# LED_MAINBOARD.net
KiCad netlist of a schematic drawn in Altium Designer
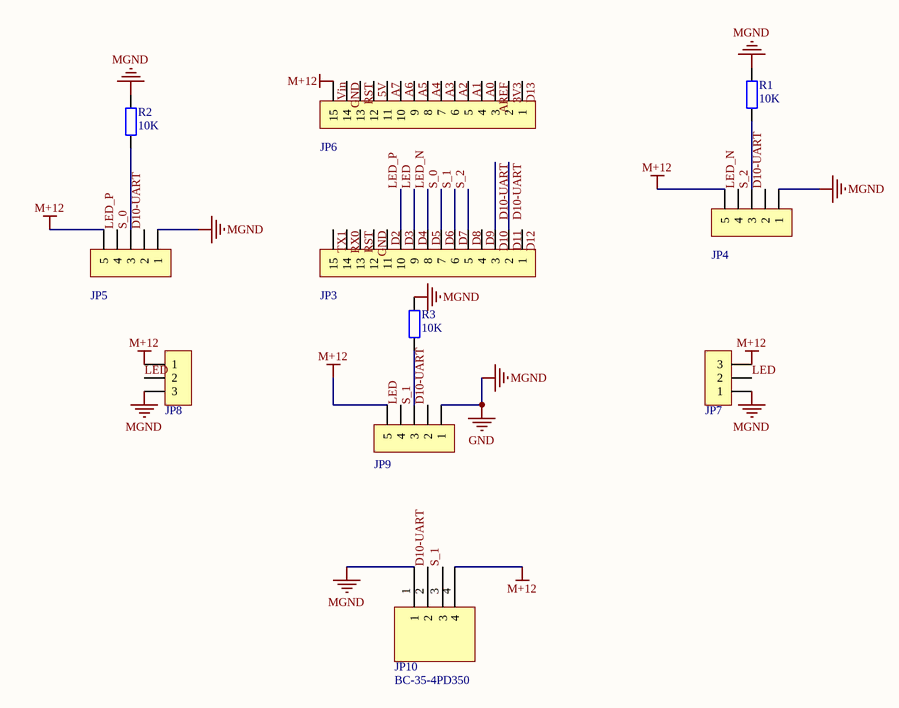
[diagram p0: LED_MAINBOARD.SchDoc]

(export (version "E")
  (design (tool "Eeschema 10.0.6"))
  (components
    (comp (ref "JP3")
      (value "HDR-1X15")
      (footprint "HDR2.54-M-LI-15P")
      (description "15P接插件")
      (fields (field (name "版权归属") "源创客"))
      (libsource (lib "4.6   - 接插件-脚距2.54") (part "Header 15"))
    )
    (comp (ref "JP4")
      (value "HDR-1X5")
      (footprint "ZH1.5-WS-5P")
      (description "5P接插件")
      (fields (field (name "版权归属") "源创客"))
      (libsource (lib "4.4   - 接插件-脚距1.5") (part "Header 5"))
    )
    (comp (ref "JP5")
      (value "HDR-1X5")
      (footprint "ZH1.5-WS-5P")
      (description "5P接插件")
      (fields (field (name "版权归属") "源创客"))
      (libsource (lib "4.4   - 接插件-脚距1.5") (part "Header 5"))
    )
    (comp (ref "JP6")
      (value "HDR-1X15")
      (footprint "HDR2.54-M-LI-15P")
      (description "15P接插件")
      (fields (field (name "版权归属") "源创客"))
      (libsource (lib "4.6   - 接插件-脚距2.54") (part "Header 15"))
    )
    (comp (ref "JP7")
      (value "HDR-1X3")
      (footprint "ZH1.5-WS-3P")
      (description "3P接插件")
      (fields (field (name "版权归属") "源创客"))
      (libsource (lib "4.4   - 接插件-脚距1.5") (part "Header 3"))
    )
    (comp (ref "JP8")
      (value "HDR-1X3")
      (footprint "ZH1.5-WS-3P")
      (description "3P接插件")
      (fields (field (name "版权归属") "源创客"))
      (libsource (lib "") (part "Header 3_1"))
    )
    (comp (ref "JP9")
      (value "HDR-1X5")
      (footprint "ZH1.5-WS-5P")
      (description "5P接插件")
      (fields (field (name "版权归属") "源创客"))
      (libsource (lib "4.4   - 接插件-脚距1.5") (part "Header 5"))
    )
    (comp (ref "JP10")
      (value "BC-35-4PD350")
      (footprint "BC-35-4PD350")
      (libsource (lib "15.1 - 未分类器件") (part "BC-35-4PD350"))
    )
    (comp (ref "R1")
      (value "10K")
      (footprint "R 0603_L")
      (description "贴片电阻")
      (fields (field (name "版权归属") "源创客"))
      (libsource (lib "3.1   - 电阻-电容-电感") (part "R"))
    )
    (comp (ref "R2")
      (value "10K")
      (footprint "R 0603_L")
      (description "贴片电阻")
      (fields (field (name "版权归属") "源创客"))
      (libsource (lib "3.1   - 电阻-电容-电感") (part "R"))
    )
    (comp (ref "R3")
      (value "10K")
      (footprint "R 0603_L")
      (description "贴片电阻")
      (fields (field (name "版权归属") "源创客"))
      (libsource (lib "3.1   - 电阻-电容-电感") (part "R"))
    )
  )
  (nets
    (net (code "1") (name "/3V3") (class "Default")
      (node (ref "JP6") (pin "2") (pinfunction "2_2") (pintype "passive"))
    )
    (net (code "2") (name "/5V") (class "Default")
      (node (ref "JP6") (pin "12") (pinfunction "12_12") (pintype "passive"))
    )
    (net (code "3") (name "/A0") (class "Default")
      (node (ref "JP6") (pin "4") (pinfunction "4_4") (pintype "passive"))
    )
    (net (code "4") (name "/A1") (class "Default")
      (node (ref "JP6") (pin "5") (pinfunction "5_5") (pintype "passive"))
    )
    (net (code "5") (name "/A2") (class "Default")
      (node (ref "JP6") (pin "6") (pinfunction "6_6") (pintype "passive"))
    )
    (net (code "6") (name "/A3") (class "Default")
      (node (ref "JP6") (pin "7") (pinfunction "7_7") (pintype "passive"))
    )
    (net (code "7") (name "/A4") (class "Default")
      (node (ref "JP6") (pin "8") (pinfunction "8_8") (pintype "passive"))
    )
    (net (code "8") (name "/A5") (class "Default")
      (node (ref "JP6") (pin "9") (pinfunction "9_9") (pintype "passive"))
    )
    (net (code "9") (name "/A6") (class "Default")
      (node (ref "JP6") (pin "10") (pinfunction "10_10") (pintype "passive"))
    )
    (net (code "10") (name "/A7") (class "Default")
      (node (ref "JP6") (pin "11") (pinfunction "11_11") (pintype "passive"))
    )
    (net (code "11") (name "/AREF") (class "Default")
      (node (ref "JP6") (pin "3") (pinfunction "3_3") (pintype "passive"))
    )
    (net (code "12") (name "/D2") (class "Default")
      (node (ref "JP3") (pin "11") (pinfunction "11_11") (pintype "passive"))
    )
    (net (code "13") (name "/D3") (class "Default")
      (node (ref "JP3") (pin "10") (pinfunction "10_10") (pintype "passive"))
      (node (ref "JP5") (pin "4") (pinfunction "4_4") (pintype "passive"))
    )
    (net (code "14") (name "/D4") (class "Default")
      (node (ref "JP3") (pin "9") (pinfunction "9_9") (pintype "passive"))
      (node (ref "JP7") (pin "2") (pinfunction "2_2") (pintype "passive"))
      (node (ref "JP8") (pin "2") (pinfunction "2_2") (pintype "passive"))
      (node (ref "JP9") (pin "4") (pinfunction "4_4") (pintype "passive"))
    )
    (net (code "15") (name "/D5") (class "Default")
      (node (ref "JP3") (pin "8") (pinfunction "8_8") (pintype "passive"))
      (node (ref "JP4") (pin "4") (pinfunction "4_4") (pintype "passive"))
    )
    (net (code "16") (name "/D6") (class "Default")
      (node (ref "JP3") (pin "7") (pinfunction "7_7") (pintype "passive"))
      (node (ref "JP5") (pin "3") (pinfunction "3_3") (pintype "passive"))
      (node (ref "R2") (pin "1") (pinfunction "1_1") (pintype "passive"))
    )
    (net (code "17") (name "/D7") (class "Default")
      (node (ref "JP10") (pin "3") (pinfunction "3_3") (pintype "passive"))
      (node (ref "JP3") (pin "6") (pinfunction "6_6") (pintype "passive"))
      (node (ref "JP9") (pin "3") (pinfunction "3_3") (pintype "passive"))
      (node (ref "R3") (pin "1") (pinfunction "1_1") (pintype "passive"))
    )
    (net (code "18") (name "/D8") (class "Default")
      (node (ref "JP3") (pin "5") (pinfunction "5_5") (pintype "passive"))
      (node (ref "JP4") (pin "3") (pinfunction "3_3") (pintype "passive"))
      (node (ref "R1") (pin "1") (pinfunction "1_1") (pintype "passive"))
    )
    (net (code "19") (name "/D9") (class "Default")
      (node (ref "JP3") (pin "4") (pinfunction "4_4") (pintype "passive"))
    )
    (net (code "20") (name "/D10") (class "Default")
      (node (ref "JP10") (pin "2") (pinfunction "2_2") (pintype "passive"))
      (node (ref "JP3") (pin "2") (pinfunction "2_2") (pintype "passive"))
      (node (ref "JP3") (pin "3") (pinfunction "3_3") (pintype "passive"))
      (node (ref "JP4") (pin "2") (pinfunction "2_2") (pintype "passive"))
      (node (ref "JP5") (pin "2") (pinfunction "2_2") (pintype "passive"))
      (node (ref "JP9") (pin "2") (pinfunction "2_2") (pintype "passive"))
    )
    (net (code "21") (name "/D12") (class "Default")
      (node (ref "JP3") (pin "1") (pinfunction "1_1") (pintype "passive"))
    )
    (net (code "22") (name "/D13") (class "Default")
      (node (ref "JP6") (pin "1") (pinfunction "1_1") (pintype "passive"))
    )
    (net (code "23") (name "/RST") (class "Default")
      (node (ref "JP3") (pin "13") (pinfunction "13_13") (pintype "passive"))
      (node (ref "JP6") (pin "13") (pinfunction "13_13") (pintype "passive"))
    )
    (net (code "24") (name "/RX0") (class "Default")
      (node (ref "JP3") (pin "14") (pinfunction "14_14") (pintype "passive"))
    )
    (net (code "25") (name "/TX1") (class "Default")
      (node (ref "JP3") (pin "15") (pinfunction "15_15") (pintype "passive"))
    )
    (net (code "26") (name "GND") (class "Default")
      (node (ref "JP10") (pin "1") (pinfunction "1_1") (pintype "passive"))
      (node (ref "JP3") (pin "12") (pinfunction "12_12") (pintype "passive"))
      (node (ref "JP4") (pin "1") (pinfunction "1_1") (pintype "passive"))
      (node (ref "JP5") (pin "1") (pinfunction "1_1") (pintype "passive"))
      (node (ref "JP6") (pin "14") (pinfunction "14_14") (pintype "passive"))
      (node (ref "JP7") (pin "1") (pinfunction "1_1") (pintype "passive"))
      (node (ref "JP8") (pin "3") (pinfunction "3_3") (pintype "passive"))
      (node (ref "JP9") (pin "1") (pinfunction "1_1") (pintype "passive"))
      (node (ref "R1") (pin "2") (pinfunction "2_2") (pintype "passive"))
      (node (ref "R2") (pin "2") (pinfunction "2_2") (pintype "passive"))
      (node (ref "R3") (pin "2") (pinfunction "2_2") (pintype "passive"))
    )
    (net (code "27") (name "M+12") (class "Default")
      (node (ref "JP10") (pin "4") (pinfunction "4_4") (pintype "passive"))
      (node (ref "JP4") (pin "5") (pinfunction "5_5") (pintype "passive"))
      (node (ref "JP5") (pin "5") (pinfunction "5_5") (pintype "passive"))
      (node (ref "JP6") (pin "15") (pinfunction "15_15") (pintype "passive"))
      (node (ref "JP7") (pin "3") (pinfunction "3_3") (pintype "passive"))
      (node (ref "JP8") (pin "1") (pinfunction "1_1") (pintype "passive"))
      (node (ref "JP9") (pin "5") (pinfunction "5_5") (pintype "passive"))
    )
  )
)
